# GSM_Signal_Control.net
KiCad netlist of a schematic drawn in Altium Designer
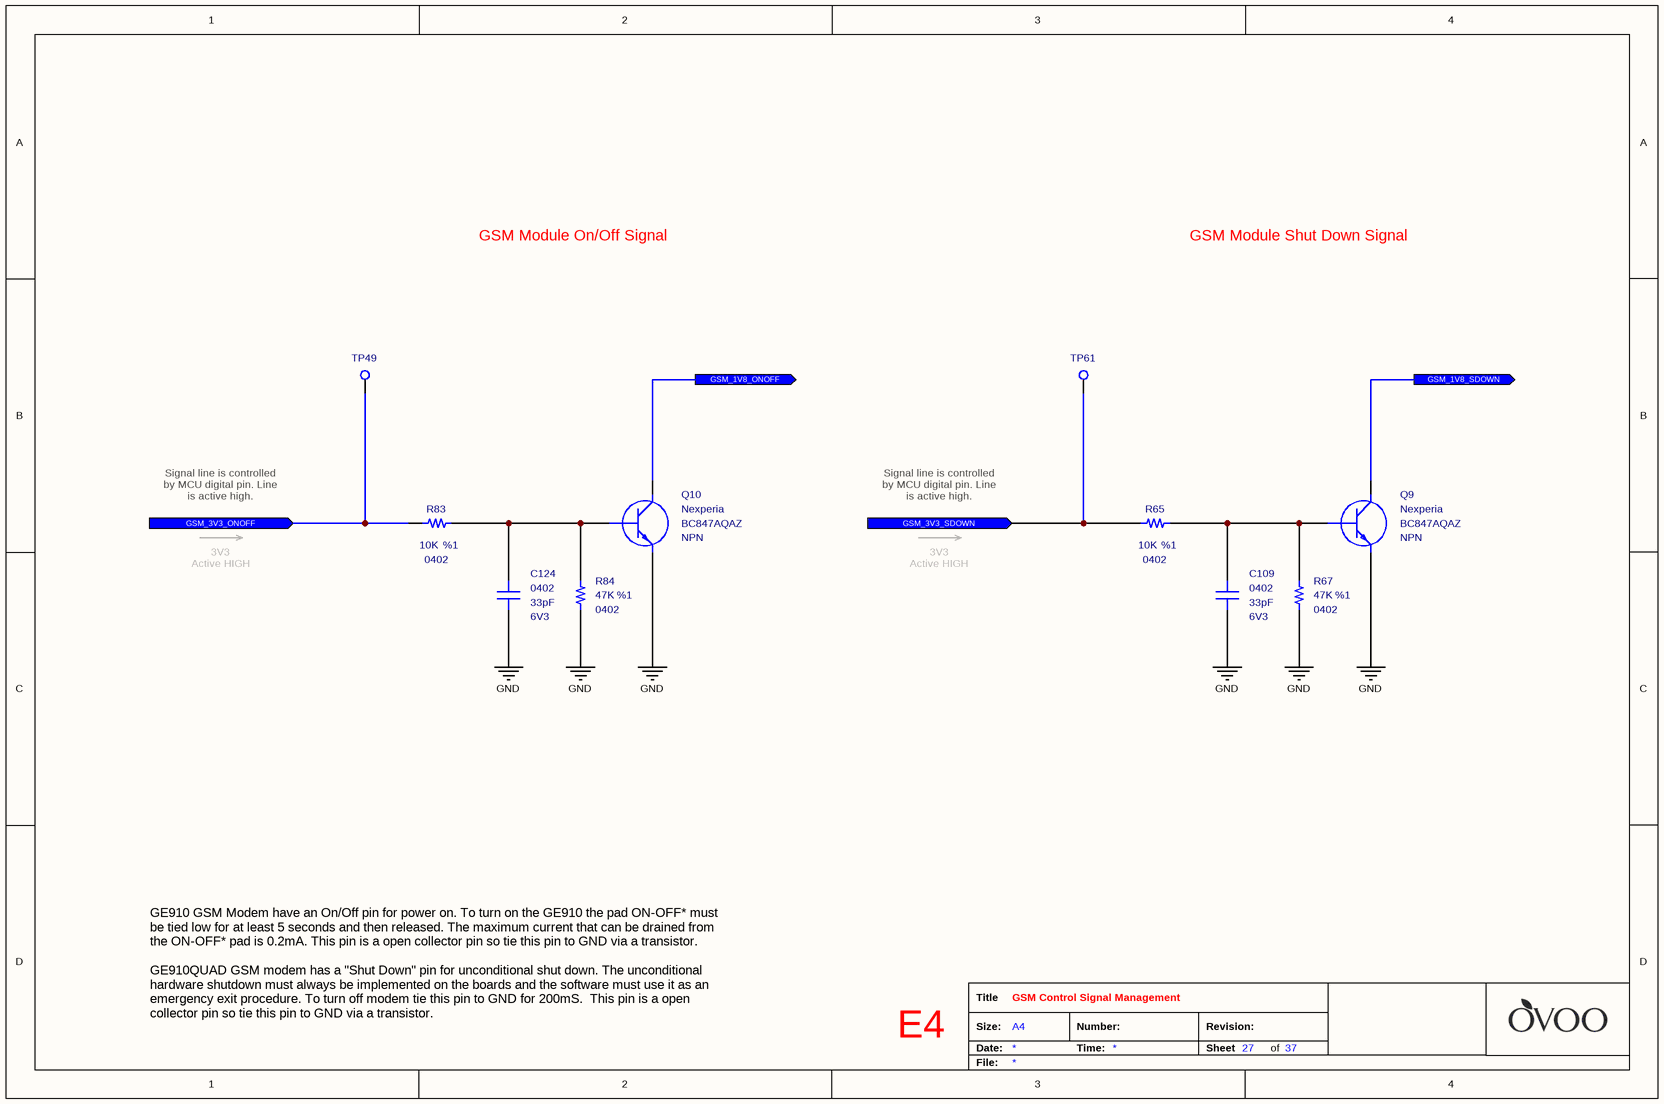
[diagram p0: GSM Signal Control.SchDoc]

(export (version "E")
  (design (tool "Eeschema 10.0.6"))
  (components
    (comp (ref "C109")
      (value "33pF")
      (footprint "CAPACITOR_0402")
      (description "Capacitor - 33pF [0402] (Ceramic)")
      (fields
        (field (name "MANUFACTURER_PART_NUMBER") "C0402C330J9RACAUTO")
        (field (name "MOUSER_PART_NUMBER") "80-C0402C330J9RAUTO")
        (field (name "CASE") "0402")
        (field (name "VOLTAGE") "6V3")
      )
      (libsource (lib "Ovoo_Schematic") (part "Capacitor - 33pF [0402-6V3]"))
    )
    (comp (ref "C124")
      (value "33pF")
      (footprint "CAPACITOR_0402")
      (description "Capacitor - 33pF [0402] (Ceramic)")
      (fields
        (field (name "MANUFACTURER_PART_NUMBER") "C0402C330J9RACAUTO")
        (field (name "MOUSER_PART_NUMBER") "80-C0402C330J9RAUTO")
        (field (name "CASE") "0402")
        (field (name "VOLTAGE") "6V3")
      )
      (libsource (lib "Ovoo_Schematic") (part "Capacitor - 33pF [0402-6V3]"))
    )
    (comp (ref "Q9")
      (value "Bipolar NPN Transistors")
      (footprint "SOT1215")
      (description "Bipolar Transistors - BJT BC847AQA/DFN1010D-3/REEL 7\" Q2")
      (fields
        (field (name "MOUSER_PART_NUMBER") "771-BC847AQAZ")
        (field (name "MANUFACTURER_NAME") "Nexperia")
        (field (name "MANUFACTURER_PART_NUMBER") "BC847AQAZ")
        (field (name "POLARITY") "NPN")
      )
      (libsource (lib "Ovoo_Schematic") (part "Transistor - BC847"))
    )
    (comp (ref "Q10")
      (value "Bipolar NPN Transistors")
      (footprint "SOT1215")
      (description "Bipolar Transistors - BJT BC847AQA/DFN1010D-3/REEL 7\" Q2")
      (fields
        (field (name "MOUSER_PART_NUMBER") "771-BC847AQAZ")
        (field (name "MANUFACTURER_NAME") "Nexperia")
        (field (name "MANUFACTURER_PART_NUMBER") "BC847AQAZ")
        (field (name "POLARITY") "NPN")
      )
      (libsource (lib "Ovoo_Schematic") (part "Transistor - BC847"))
    )
    (comp (ref "R65")
      (value "10K")
      (footprint "RESISTOR_0402")
      (description "Thick Film Resistors - SMD 1/16 W 10 Kohms 1%")
      (fields
        (field (name "MANUFACTURER_PART_NUMBER") "CRCW040210K0FKED")
        (field (name "MOUSER_PART_NUMBER") "71-CRCW0402-10K-E3")
        (field (name "TOLERANCE") "%1")
        (field (name "CASE") "0402")
      )
      (libsource (lib "Ovoo_Schematic") (part "Resistor - 10K"))
    )
    (comp (ref "R67")
      (value "47K")
      (footprint "RESISTOR_0402")
      (description "Thick Film Resistors - SMD 1/16 W 47 Kohms 1%")
      (fields
        (field (name "MANUFACTURER_PART_NUMBER") "CRCW040247K0FKED")
        (field (name "MOUSER_PART_NUMBER") "71-CRCW0402-47K-E3")
        (field (name "TOLERANCE") "%1")
        (field (name "CASE") "0402")
      )
      (libsource (lib "Ovoo_Schematic") (part "Resistor - 47K"))
    )
    (comp (ref "R83")
      (value "10K")
      (footprint "RESISTOR_0402")
      (description "Thick Film Resistors - SMD 1/16 W 10 Kohms 1%")
      (fields
        (field (name "MANUFACTURER_PART_NUMBER") "CRCW040210K0FKED")
        (field (name "MOUSER_PART_NUMBER") "71-CRCW0402-10K-E3")
        (field (name "TOLERANCE") "%1")
        (field (name "CASE") "0402")
      )
      (libsource (lib "Ovoo_Schematic") (part "Resistor - 10K"))
    )
    (comp (ref "R84")
      (value "47K")
      (footprint "RESISTOR_0402")
      (description "Thick Film Resistors - SMD 1/16 W 47 Kohms 1%")
      (fields
        (field (name "MANUFACTURER_PART_NUMBER") "CRCW040247K0FKED")
        (field (name "MOUSER_PART_NUMBER") "71-CRCW0402-47K-E3")
        (field (name "TOLERANCE") "%1")
        (field (name "CASE") "0402")
      )
      (libsource (lib "Ovoo_Schematic") (part "Resistor - 47K"))
    )
    (comp (ref "TP49")
      (value "PCB - Test Point")
      (footprint "Test_Pad - Hole")
      (description "Test Point")
      (libsource (lib "Ovoo_Schematic") (part "PCB - Test Point"))
    )
    (comp (ref "TP61")
      (value "PCB - Test Point")
      (footprint "Test_Pad - Hole")
      (description "Test Point")
      (libsource (lib "Ovoo_Schematic") (part "PCB - Test Point"))
    )
  )
  (nets
    (net (code "1") (name "/GSM_1V8_ONOFF") (class "Default")
      (node (ref "Q10") (pin "3") (pinfunction "C_3") (pintype "passive"))
    )
    (net (code "2") (name "/GSM_1V8_SDOWN") (class "Default")
      (node (ref "Q9") (pin "3") (pinfunction "C_3") (pintype "passive"))
    )
    (net (code "3") (name "/GSM_3V3_ONOFF") (class "Default")
      (node (ref "R83") (pin "2") (pinfunction "2_2") (pintype "passive"))
      (node (ref "TP49") (pin "1") (pinfunction "1_1") (pintype "passive"))
    )
    (net (code "4") (name "/GSM_3V3_SDOWN") (class "Default")
      (node (ref "R65") (pin "2") (pinfunction "2_2") (pintype "passive"))
      (node (ref "TP61") (pin "1") (pinfunction "1_1") (pintype "passive"))
    )
    (net (code "5") (name "GND") (class "Default")
      (node (ref "C109") (pin "2") (pinfunction "2_2") (pintype "passive"))
      (node (ref "C124") (pin "2") (pinfunction "2_2") (pintype "passive"))
      (node (ref "Q10") (pin "2") (pinfunction "E_2") (pintype "passive"))
      (node (ref "Q9") (pin "2") (pinfunction "E_2") (pintype "passive"))
      (node (ref "R67") (pin "1") (pinfunction "1_1") (pintype "passive"))
      (node (ref "R84") (pin "1") (pinfunction "1_1") (pintype "passive"))
    )
    (net (code "6") (name "Net-(Q9-B)") (class "Default")
      (node (ref "C109") (pin "1") (pinfunction "1_1") (pintype "passive"))
      (node (ref "Q9") (pin "1") (pinfunction "B_1") (pintype "passive"))
      (node (ref "R65") (pin "1") (pinfunction "1_1") (pintype "passive"))
      (node (ref "R67") (pin "2") (pinfunction "2_2") (pintype "passive"))
    )
    (net (code "7") (name "Net-(Q10-B)") (class "Default")
      (node (ref "C124") (pin "1") (pinfunction "1_1") (pintype "passive"))
      (node (ref "Q10") (pin "1") (pinfunction "B_1") (pintype "passive"))
      (node (ref "R83") (pin "1") (pinfunction "1_1") (pintype "passive"))
      (node (ref "R84") (pin "2") (pinfunction "2_2") (pintype "passive"))
    )
  )
)
